# Platine_2.net
KiCad netlist of a schematic drawn in EAGLE
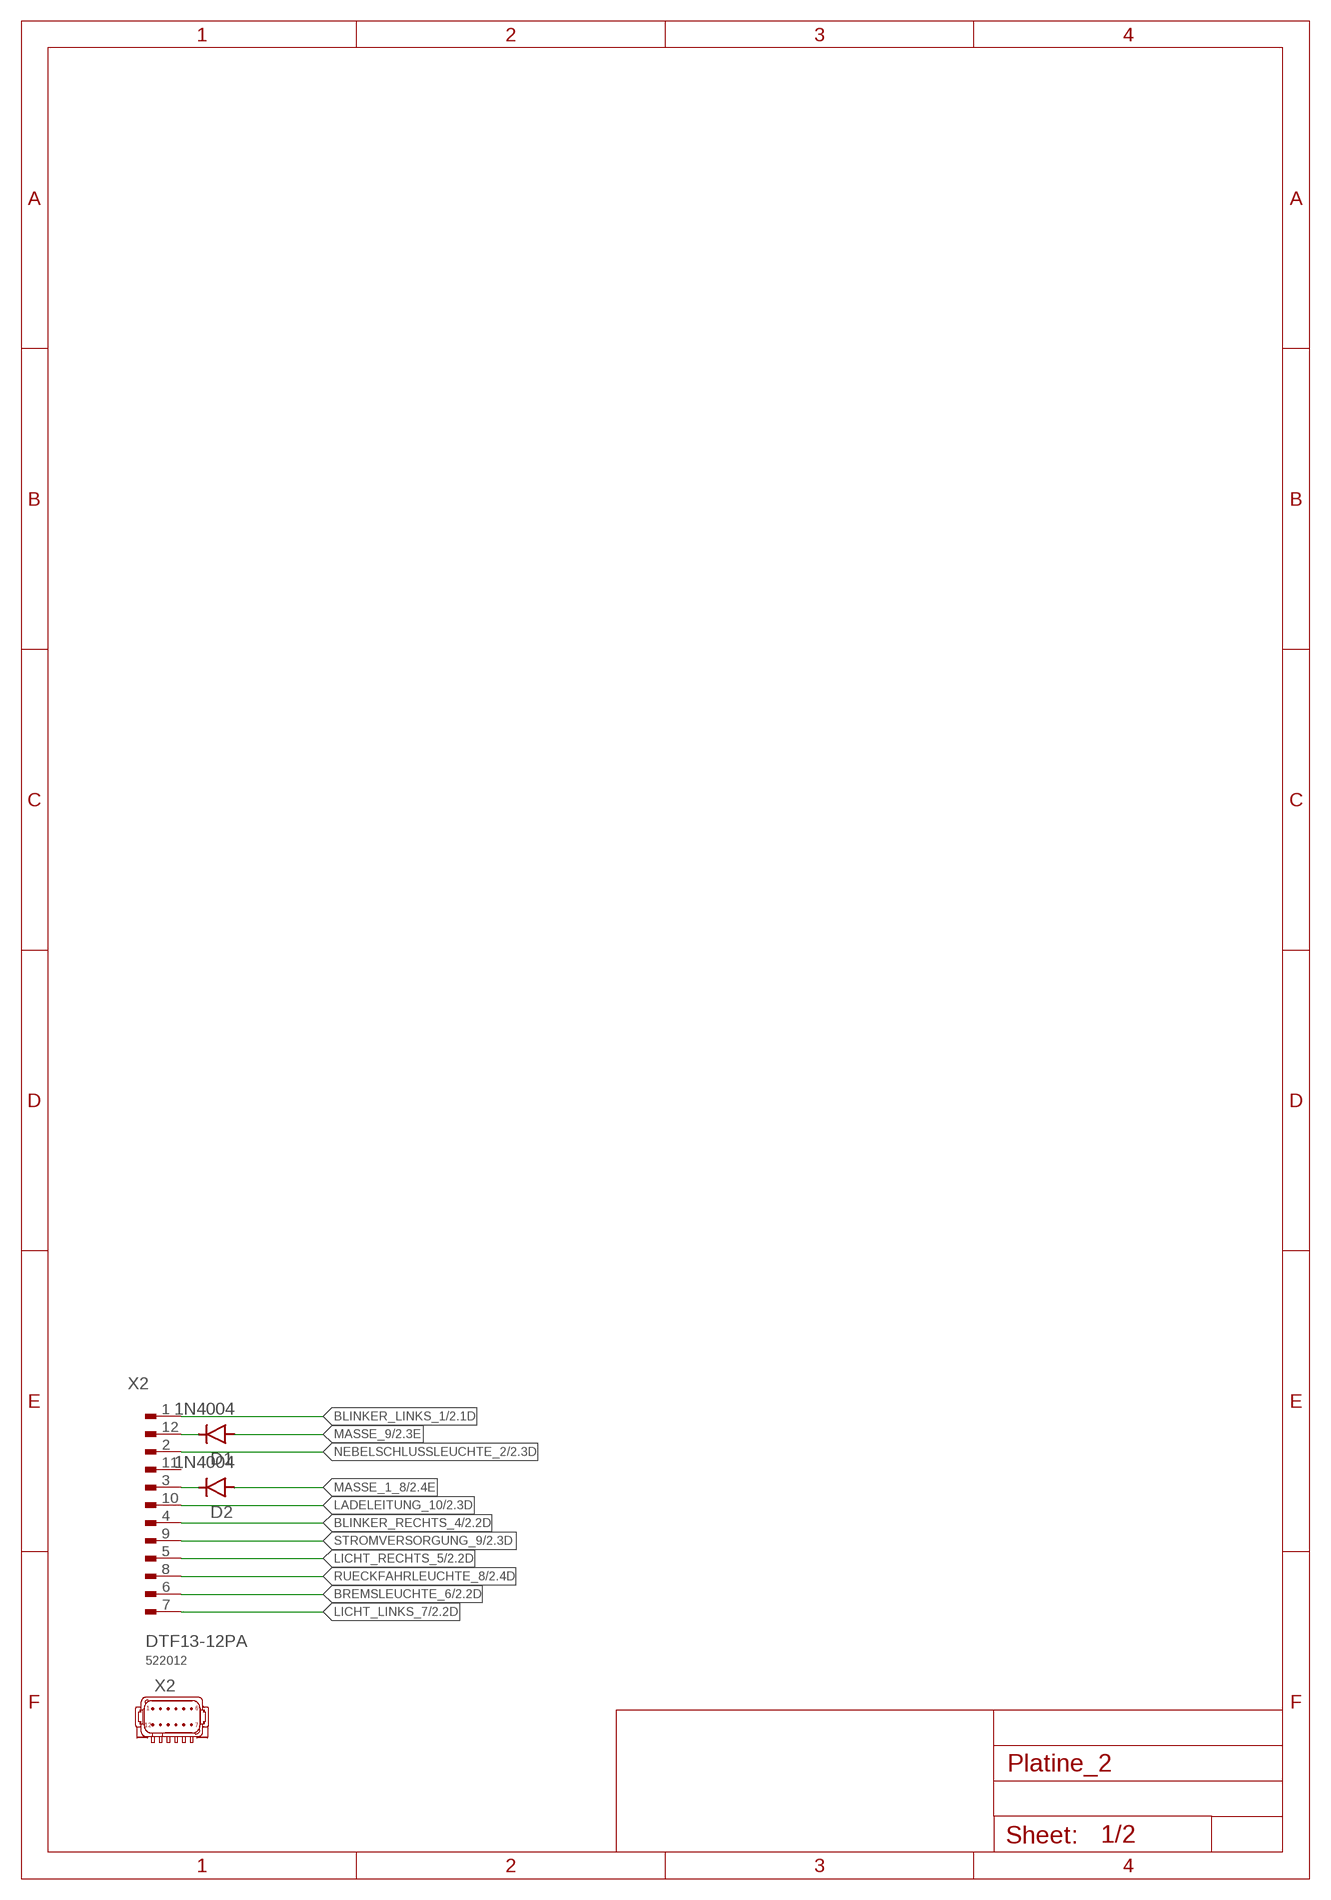
[diagram p0: schematic, sheet 1]
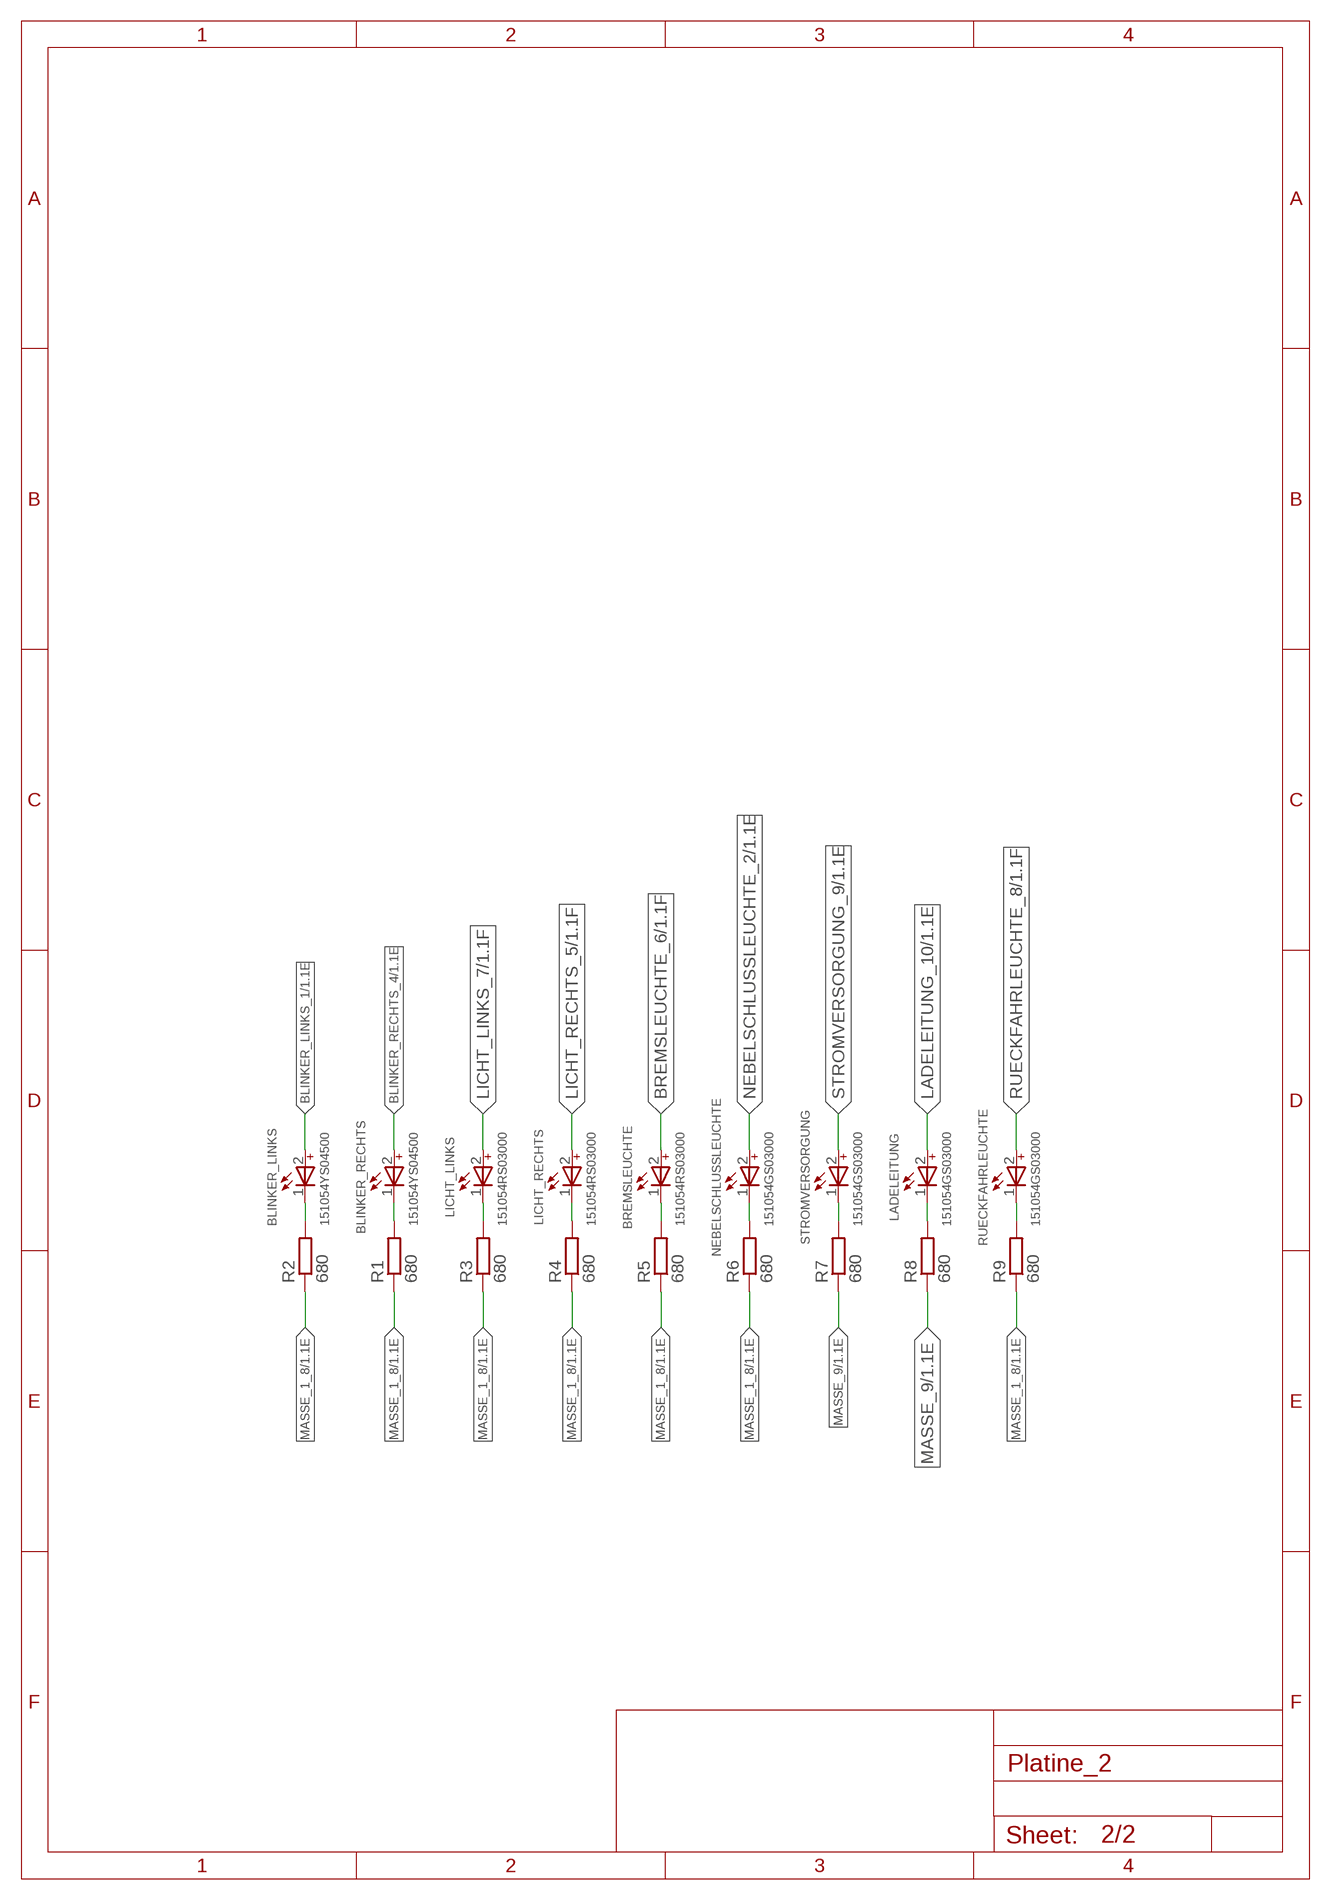
[diagram p1: schematic, sheet 2]

(export (version "E")
  (design (tool "Eeschema 10.0.6"))
  (components
    (comp (ref "BLINKER_LINKS")
      (value "151054YS04500")
      (footprint "eagle-import:WL-TMRW_5MM")
      (libsource (lib "eagle-import") (part "WL-TMRW_5MM_WITHOUTSTOPPER_151054YS04500"))
    )
    (comp (ref "BLINKER_RECHTS")
      (value "151054YS04500")
      (footprint "eagle-import:WL-TMRW_5MM")
      (libsource (lib "eagle-import") (part "WL-TMRW_5MM_WITHOUTSTOPPER_151054YS04500"))
    )
    (comp (ref "BREMSLEUCHTE")
      (value "151054RS03000")
      (footprint "eagle-import:WL-TMRW_5MM")
      (libsource (lib "eagle-import") (part "WL-TMRW_5MM_WITHOUTSTOPPER_151054RS03000"))
    )
    (comp (ref "LADELEITUNG")
      (value "151054GS03000")
      (footprint "eagle-import:WL-TMRW_5MM")
      (libsource (lib "eagle-import") (part "WL-TMRW_5MM_WITHOUTSTOPPER_151054GS03000"))
    )
    (comp (ref "LICHT_LINKS")
      (value "151054RS03000")
      (footprint "eagle-import:WL-TMRW_5MM")
      (libsource (lib "eagle-import") (part "WL-TMRW_5MM_WITHOUTSTOPPER_151054RS03000"))
    )
    (comp (ref "LICHT_RECHTS")
      (value "151054RS03000")
      (footprint "eagle-import:WL-TMRW_5MM")
      (libsource (lib "eagle-import") (part "WL-TMRW_5MM_WITHOUTSTOPPER_151054RS03000"))
    )
    (comp (ref "NEBELSCHLUSSLEUCHTE")
      (value "151054GS03000")
      (footprint "eagle-import:WL-TMRW_5MM")
      (libsource (lib "eagle-import") (part "WL-TMRW_5MM_WITHOUTSTOPPER_151054GS03000"))
    )
    (comp (ref "R1")
      (value "680")
      (footprint "eagle-import:0207_10")
      (libsource (lib "eagle-import") (part "R-EU_0207/10"))
    )
    (comp (ref "R2")
      (value "680")
      (footprint "eagle-import:0207_10")
      (libsource (lib "eagle-import") (part "R-EU_0207/10"))
    )
    (comp (ref "R3")
      (value "680")
      (footprint "eagle-import:0207_10")
      (libsource (lib "eagle-import") (part "R-EU_0207/10"))
    )
    (comp (ref "R4")
      (value "680")
      (footprint "eagle-import:0207_10")
      (libsource (lib "eagle-import") (part "R-EU_0207/10"))
    )
    (comp (ref "R5")
      (value "680")
      (footprint "eagle-import:0207_10")
      (libsource (lib "eagle-import") (part "R-EU_0207/10"))
    )
    (comp (ref "R6")
      (value "680")
      (footprint "eagle-import:0207_10")
      (libsource (lib "eagle-import") (part "R-EU_0207/10"))
    )
    (comp (ref "R7")
      (value "680")
      (footprint "eagle-import:0207_10")
      (libsource (lib "eagle-import") (part "R-EU_0207/10"))
    )
    (comp (ref "R8")
      (value "680")
      (footprint "eagle-import:0207_10")
      (libsource (lib "eagle-import") (part "R-EU_0207/10"))
    )
    (comp (ref "R9")
      (value "680")
      (footprint "eagle-import:0204_7")
      (libsource (lib "eagle-import") (part "resistor_348_R-EU_0204/7"))
    )
    (comp (ref "RUECKFAHRLEUCHTE")
      (value "151054GS03000")
      (footprint "eagle-import:WL-TMRW_5MM")
      (libsource (lib "eagle-import") (part "WL-TMRW_5MM_WITHOUTSTOPPER_151054GS03000"))
    )
    (comp (ref "STROMVERSORGUNG")
      (value "151054GS03000")
      (footprint "eagle-import:WL-TMRW_5MM")
      (libsource (lib "eagle-import") (part "WL-TMRW_5MM_WITHOUTSTOPPER_151054GS03000"))
    )
    (comp (ref "D1")
      (value "1N4004")
      (footprint "eagle-import:DO-41")
      (fields
        (field (name "DIGIKEY_PART_NUMBER") "1N4004MSCT-ND")
        (field (name "MANUFACTURER") "Micro Commercial Co")
        (field (name "CREATED_BY") "PCBLayout.com")
      )
      (libsource (lib "eagle-import") (part "1N4004"))
    )
    (comp (ref "D2")
      (value "1N4004")
      (footprint "eagle-import:DO-41")
      (fields
        (field (name "DIGIKEY_PART_NUMBER") "1N4004MSCT-ND")
        (field (name "MANUFACTURER") "Micro Commercial Co")
        (field (name "CREATED_BY") "PCBLayout.com")
      )
      (libsource (lib "eagle-import") (part "1N4004"))
    )
    (comp (ref "X2")
      (value "DTF13-12PA")
      (footprint "eagle-import:DTF13-12PA")
      (fields (field (name "ARTIKEL_NR") "522012"))
      (libsource (lib "eagle-import") (part "DTF13-12PA"))
    )
  )
  (nets
    (net (code "1") (name "BLINKER_LINKS_1") (class "Default")
      (node (ref "BLINKER_LINKS") (pin "2") (pinfunction "+_2") (pintype "passive"))
      (node (ref "X2") (pin "1") (pinfunction "1_1") (pintype "passive"))
    )
    (net (code "2") (name "BLINKER_RECHTS_4") (class "Default")
      (node (ref "BLINKER_RECHTS") (pin "2") (pinfunction "+_2") (pintype "passive"))
      (node (ref "X2") (pin "4") (pinfunction "4_4") (pintype "passive"))
    )
    (net (code "3") (name "BREMSLEUCHTE_6") (class "Default")
      (node (ref "BREMSLEUCHTE") (pin "2") (pinfunction "+_2") (pintype "passive"))
      (node (ref "X2") (pin "6") (pinfunction "6_6") (pintype "passive"))
    )
    (net (code "4") (name "LADELEITUNG_10") (class "Default")
      (node (ref "LADELEITUNG") (pin "2") (pinfunction "+_2") (pintype "passive"))
      (node (ref "X2") (pin "10") (pinfunction "10_10") (pintype "passive"))
    )
    (net (code "5") (name "LICHT_LINKS_7") (class "Default")
      (node (ref "LICHT_LINKS") (pin "2") (pinfunction "+_2") (pintype "passive"))
      (node (ref "X2") (pin "7") (pinfunction "7_7") (pintype "passive"))
    )
    (net (code "6") (name "LICHT_RECHTS_5") (class "Default")
      (node (ref "LICHT_RECHTS") (pin "2") (pinfunction "+_2") (pintype "passive"))
      (node (ref "X2") (pin "5") (pinfunction "5_5") (pintype "passive"))
    )
    (net (code "7") (name "MASSE_1_8") (class "Default")
      (node (ref "D2") (pin "A") (pinfunction "A_A") (pintype "passive"))
      (node (ref "R1") (pin "1") (pinfunction "1_1") (pintype "passive"))
      (node (ref "R2") (pin "1") (pinfunction "1_1") (pintype "passive"))
      (node (ref "R3") (pin "1") (pinfunction "1_1") (pintype "passive"))
      (node (ref "R4") (pin "1") (pinfunction "1_1") (pintype "passive"))
      (node (ref "R5") (pin "1") (pinfunction "1_1") (pintype "passive"))
      (node (ref "R6") (pin "1") (pinfunction "1_1") (pintype "passive"))
      (node (ref "R9") (pin "1") (pinfunction "1_1") (pintype "passive"))
    )
    (net (code "8") (name "MASSE_9") (class "Default")
      (node (ref "D1") (pin "A") (pinfunction "A_A") (pintype "passive"))
      (node (ref "R7") (pin "1") (pinfunction "1_1") (pintype "passive"))
      (node (ref "R8") (pin "1") (pinfunction "1_1") (pintype "passive"))
    )
    (net (code "9") (name "NEBELSCHLUSSLEUCHTE_2") (class "Default")
      (node (ref "NEBELSCHLUSSLEUCHTE") (pin "2") (pinfunction "+_2") (pintype "passive"))
      (node (ref "X2") (pin "2") (pinfunction "2_2") (pintype "passive"))
    )
    (net (code "10") (name "Net-(BLINKER_LINKS--)") (class "Default")
      (node (ref "BLINKER_LINKS") (pin "1") (pinfunction "-_1") (pintype "passive"))
      (node (ref "R2") (pin "2") (pinfunction "2_2") (pintype "passive"))
    )
    (net (code "11") (name "Net-(BLINKER_RECHTS--)") (class "Default")
      (node (ref "BLINKER_RECHTS") (pin "1") (pinfunction "-_1") (pintype "passive"))
      (node (ref "R1") (pin "2") (pinfunction "2_2") (pintype "passive"))
    )
    (net (code "12") (name "Net-(BREMSLEUCHTE--)") (class "Default")
      (node (ref "BREMSLEUCHTE") (pin "1") (pinfunction "-_1") (pintype "passive"))
      (node (ref "R5") (pin "2") (pinfunction "2_2") (pintype "passive"))
    )
    (net (code "13") (name "Net-(D1-PadC)") (class "Default")
      (node (ref "D1") (pin "C") (pinfunction "C_C") (pintype "passive"))
      (node (ref "X2") (pin "12") (pinfunction "12_12") (pintype "passive"))
    )
    (net (code "14") (name "Net-(D2-PadC)") (class "Default")
      (node (ref "D2") (pin "C") (pinfunction "C_C") (pintype "passive"))
      (node (ref "X2") (pin "3") (pinfunction "3_3") (pintype "passive"))
    )
    (net (code "15") (name "Net-(LADELEITUNG--)") (class "Default")
      (node (ref "LADELEITUNG") (pin "1") (pinfunction "-_1") (pintype "passive"))
      (node (ref "R8") (pin "2") (pinfunction "2_2") (pintype "passive"))
    )
    (net (code "16") (name "Net-(LICHT_LINKS--)") (class "Default")
      (node (ref "LICHT_LINKS") (pin "1") (pinfunction "-_1") (pintype "passive"))
      (node (ref "R3") (pin "2") (pinfunction "2_2") (pintype "passive"))
    )
    (net (code "17") (name "Net-(LICHT_RECHTS--)") (class "Default")
      (node (ref "LICHT_RECHTS") (pin "1") (pinfunction "-_1") (pintype "passive"))
      (node (ref "R4") (pin "2") (pinfunction "2_2") (pintype "passive"))
    )
    (net (code "18") (name "Net-(NEBELSCHLUSSLEUCHTE--)") (class "Default")
      (node (ref "NEBELSCHLUSSLEUCHTE") (pin "1") (pinfunction "-_1") (pintype "passive"))
      (node (ref "R6") (pin "2") (pinfunction "2_2") (pintype "passive"))
    )
    (net (code "19") (name "Net-(RUECKFAHRLEUCHTE--)") (class "Default")
      (node (ref "R9") (pin "2") (pinfunction "2_2") (pintype "passive"))
      (node (ref "RUECKFAHRLEUCHTE") (pin "1") (pinfunction "-_1") (pintype "passive"))
    )
    (net (code "20") (name "Net-(STROMVERSORGUNG--)") (class "Default")
      (node (ref "R7") (pin "2") (pinfunction "2_2") (pintype "passive"))
      (node (ref "STROMVERSORGUNG") (pin "1") (pinfunction "-_1") (pintype "passive"))
    )
    (net (code "21") (name "RUECKFAHRLEUCHTE_8") (class "Default")
      (node (ref "RUECKFAHRLEUCHTE") (pin "2") (pinfunction "+_2") (pintype "passive"))
      (node (ref "X2") (pin "8") (pinfunction "8_8") (pintype "passive"))
    )
    (net (code "22") (name "STROMVERSORGUNG_9") (class "Default")
      (node (ref "STROMVERSORGUNG") (pin "2") (pinfunction "+_2") (pintype "passive"))
      (node (ref "X2") (pin "9") (pinfunction "9_9") (pintype "passive"))
    )
    (net (code "23") (name "unconnected-(X2-Pad11)") (class "Default")
      (node (ref "X2") (pin "11") (pinfunction "11_11") (pintype "passive"))
    )
  )
)
